# lv_io_main_connector.net
KiCad netlist of a schematic drawn in Altium Designer
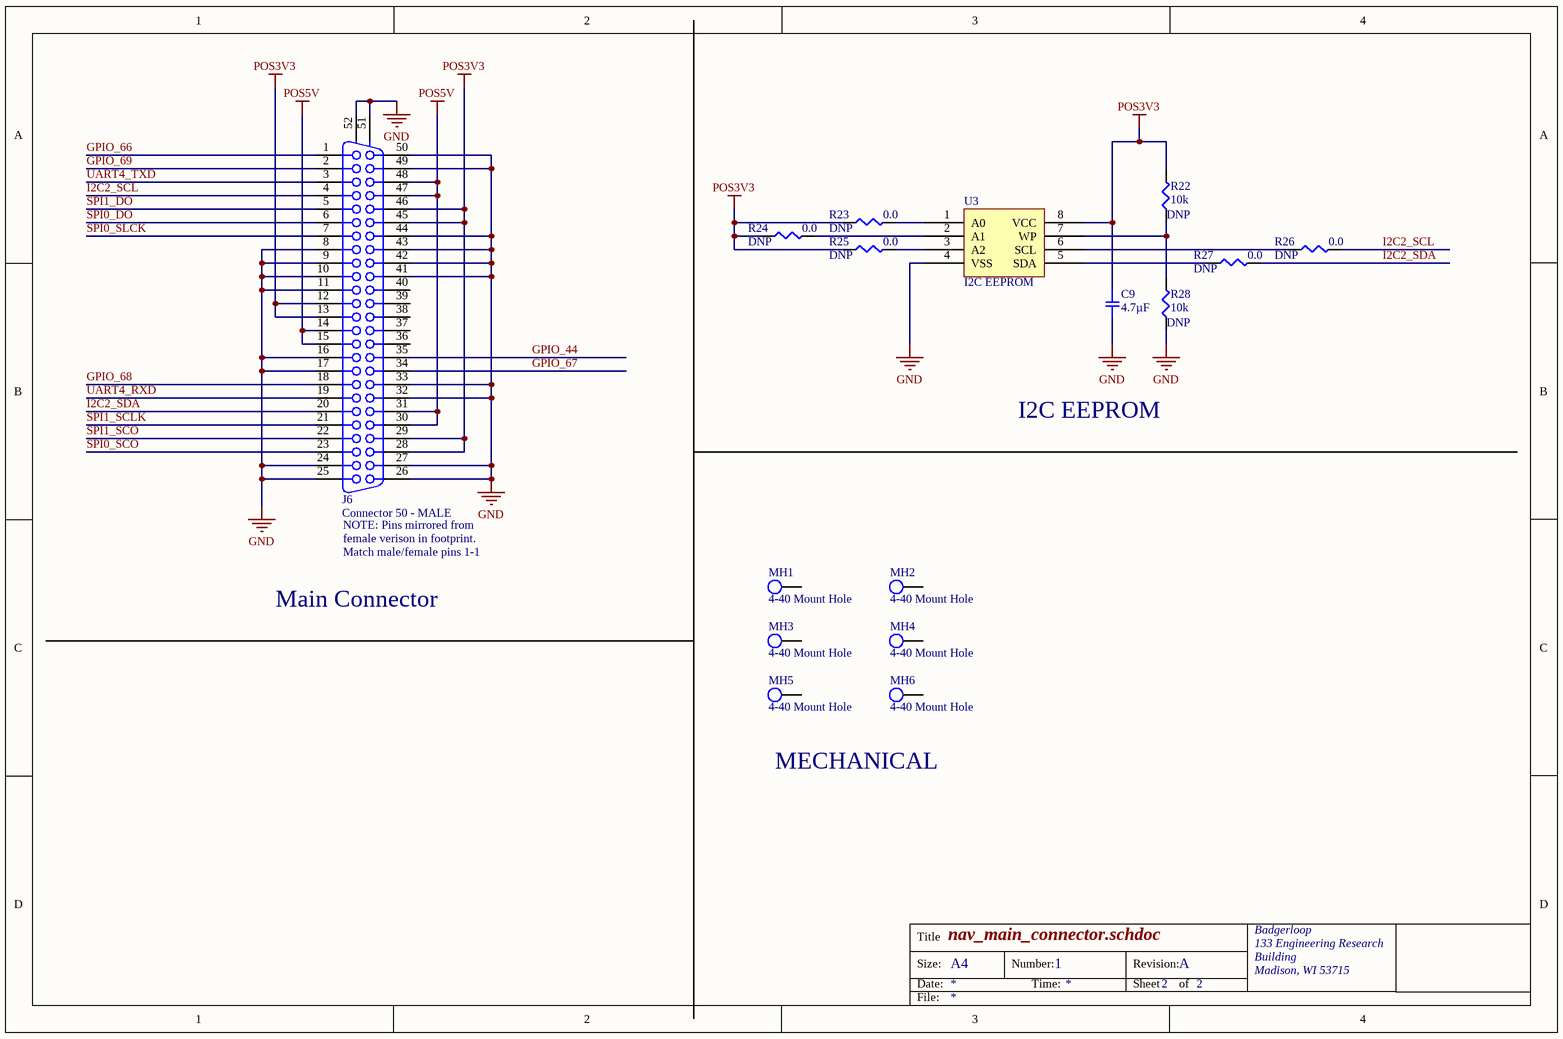
[diagram p0: lv_io_main_connector.SchDoc]

(export (version "E")
  (design (tool "Eeschema 10.0.6"))
  (components
    (comp (ref "C9")
      (value "4.7µF")
      (footprint "SMD-0805C")
      (description "CAP CER 4.7UF 16V X7R 0805")
      (fields
        (field (name "DIGI-KEY PART NUMBER") "490-10557-1-ND")
        (field (name "PART NUMBER") "GCJ21BR71C475KA01L")
      )
      (libsource (lib "capacitor") (part "GCJ21BR71C475KA01L"))
    )
    (comp (ref "J6")
      (value "Connector 50 - MALE")
      (footprint "050DSUB1.27-H96-MALE")
      (description "Receptacle Header Assemby")
      (fields (field (name "MANUFACTURER") "HARTING"))
      (libsource (lib "temp") (part "Connector 50 - MALE"))
    )
    (comp (ref "MH1")
      (value "4-40 Mount Hole")
      (footprint "MH")
      (libsource (lib "misc") (part "4-40 Mount Hole"))
    )
    (comp (ref "MH2")
      (value "4-40 Mount Hole")
      (footprint "MH")
      (libsource (lib "misc") (part "4-40 Mount Hole"))
    )
    (comp (ref "MH3")
      (value "4-40 Mount Hole")
      (footprint "MH")
      (libsource (lib "misc") (part "4-40 Mount Hole"))
    )
    (comp (ref "MH4")
      (value "4-40 Mount Hole")
      (footprint "MH")
      (libsource (lib "misc") (part "4-40 Mount Hole"))
    )
    (comp (ref "MH5")
      (value "4-40 Mount Hole")
      (footprint "MH")
      (libsource (lib "misc") (part "4-40 Mount Hole"))
    )
    (comp (ref "MH6")
      (value "4-40 Mount Hole")
      (footprint "MH")
      (libsource (lib "misc") (part "4-40 Mount Hole"))
    )
    (comp (ref "R22")
      (value "10k")
      (footprint "SMD-0402-RES")
      (description "RES SMD 10K OHM 5% 1/10W 0402")
      (fields
        (field (name "PART NUMBER") "ERJ-2GEJ103X")
        (field (name "DIGI-KEY PART NUMBER") "P10KJCT-ND")
        (field (name "DNP") "DNP")
      )
      (libsource (lib "resistor") (part "ERJ-2GEJ103X"))
    )
    (comp (ref "R23")
      (value "0.0")
      (footprint "SMD-0402-RES")
      (description "RES SMD 0.0OHM JUMPER 1/10W 0402")
      (fields
        (field (name "PART NUMBER") "ERJ-2GE0R00X")
        (field (name "DIGI-KEY PART NUMBER") "P0.0JCT-ND")
        (field (name "DNP") "DNP")
      )
      (libsource (lib "resistor") (part "ERJ-2GE0R00X"))
    )
    (comp (ref "R24")
      (value "0.0")
      (footprint "SMD-0402-RES")
      (description "RES SMD 0.0OHM JUMPER 1/10W 0402")
      (fields
        (field (name "PART NUMBER") "ERJ-2GE0R00X")
        (field (name "DIGI-KEY PART NUMBER") "P0.0JCT-ND")
        (field (name "DNP") "DNP")
      )
      (libsource (lib "resistor") (part "ERJ-2GE0R00X"))
    )
    (comp (ref "R25")
      (value "0.0")
      (footprint "SMD-0402-RES")
      (description "RES SMD 0.0OHM JUMPER 1/10W 0402")
      (fields
        (field (name "PART NUMBER") "ERJ-2GE0R00X")
        (field (name "DIGI-KEY PART NUMBER") "P0.0JCT-ND")
        (field (name "DNP") "DNP")
      )
      (libsource (lib "resistor") (part "ERJ-2GE0R00X"))
    )
    (comp (ref "R26")
      (value "0.0")
      (footprint "SMD-0402-RES")
      (description "RES SMD 0.0OHM JUMPER 1/10W 0402")
      (fields
        (field (name "PART NUMBER") "ERJ-2GE0R00X")
        (field (name "DIGI-KEY PART NUMBER") "P0.0JCT-ND")
        (field (name "DNP") "DNP")
      )
      (libsource (lib "resistor") (part "ERJ-2GE0R00X"))
    )
    (comp (ref "R27")
      (value "0.0")
      (footprint "SMD-0402-RES")
      (description "RES SMD 0.0OHM JUMPER 1/10W 0402")
      (fields
        (field (name "PART NUMBER") "ERJ-2GE0R00X")
        (field (name "DIGI-KEY PART NUMBER") "P0.0JCT-ND")
        (field (name "DNP") "DNP")
      )
      (libsource (lib "resistor") (part "ERJ-2GE0R00X"))
    )
    (comp (ref "R28")
      (value "10k")
      (footprint "SMD-0402-RES")
      (description "RES SMD 10K OHM 5% 1/10W 0402")
      (fields
        (field (name "PART NUMBER") "ERJ-2GEJ103X")
        (field (name "DIGI-KEY PART NUMBER") "P10KJCT-ND")
        (field (name "DNP") "DNP")
      )
      (libsource (lib "resistor") (part "ERJ-2GEJ103X"))
    )
    (comp (ref "U3")
      (value "I2C EEPROM")
      (footprint "SOIC127P600X175-8N")
      (description "IC EEPROM 32K I2C 1MHZ 8SOIC")
      (fields (field (name "MANUFACTURER") "ON Semi"))
      (libsource (lib "ic") (part "I2C EEPROM"))
    )
  )
  (nets
    (net (code "1") (name "/GPIO_44") (class "Default")
      (node (ref "J6") (pin "35") (pinfunction "35_35") (pintype "passive"))
    )
    (net (code "2") (name "/GPIO_66") (class "Default")
      (node (ref "J6") (pin "1") (pinfunction "1_1") (pintype "passive"))
    )
    (net (code "3") (name "/GPIO_67") (class "Default")
      (node (ref "J6") (pin "34") (pinfunction "34_34") (pintype "passive"))
    )
    (net (code "4") (name "/GPIO_68") (class "Default")
      (node (ref "J6") (pin "18") (pinfunction "18_18") (pintype "passive"))
    )
    (net (code "5") (name "/GPIO_69") (class "Default")
      (node (ref "J6") (pin "2") (pinfunction "2_2") (pintype "passive"))
    )
    (net (code "6") (name "/I2C2_SCL") (class "Default")
      (node (ref "J6") (pin "4") (pinfunction "4_4") (pintype "passive"))
      (node (ref "R26") (pin "2") (pinfunction "2_2") (pintype "passive"))
    )
    (net (code "7") (name "/I2C2_SDA") (class "Default")
      (node (ref "J6") (pin "20") (pinfunction "20_20") (pintype "passive"))
      (node (ref "R27") (pin "2") (pinfunction "2_2") (pintype "passive"))
    )
    (net (code "8") (name "/SPI0_DO") (class "Default")
      (node (ref "J6") (pin "6") (pinfunction "6_6") (pintype "passive"))
    )
    (net (code "9") (name "/SPI0_SCO") (class "Default")
      (node (ref "J6") (pin "23") (pinfunction "23_23") (pintype "passive"))
    )
    (net (code "10") (name "/SPI0_SLCK") (class "Default")
      (node (ref "J6") (pin "7") (pinfunction "7_7") (pintype "passive"))
    )
    (net (code "11") (name "/SPI1_DO") (class "Default")
      (node (ref "J6") (pin "5") (pinfunction "5_5") (pintype "passive"))
    )
    (net (code "12") (name "/SPI1_SCLK") (class "Default")
      (node (ref "J6") (pin "21") (pinfunction "21_21") (pintype "passive"))
    )
    (net (code "13") (name "/SPI1_SCO") (class "Default")
      (node (ref "J6") (pin "22") (pinfunction "22_22") (pintype "passive"))
    )
    (net (code "14") (name "/UART4_RXD") (class "Default")
      (node (ref "J6") (pin "19") (pinfunction "19_19") (pintype "passive"))
    )
    (net (code "15") (name "/UART4_TXD") (class "Default")
      (node (ref "J6") (pin "3") (pinfunction "3_3") (pintype "passive"))
    )
    (net (code "16") (name "GND") (class "Default")
      (node (ref "C9") (pin "2") (pinfunction "2_2") (pintype "passive"))
      (node (ref "J6") (pin "10") (pinfunction "10_10") (pintype "passive"))
      (node (ref "J6") (pin "11") (pinfunction "11_11") (pintype "passive"))
      (node (ref "J6") (pin "16") (pinfunction "16_16") (pintype "passive"))
      (node (ref "J6") (pin "17") (pinfunction "17_17") (pintype "passive"))
      (node (ref "J6") (pin "24") (pinfunction "24_24") (pintype "passive"))
      (node (ref "J6") (pin "25") (pinfunction "25_25") (pintype "passive"))
      (node (ref "J6") (pin "26") (pinfunction "26_26") (pintype "passive"))
      (node (ref "J6") (pin "27") (pinfunction "27_27") (pintype "passive"))
      (node (ref "J6") (pin "32") (pinfunction "32_32") (pintype "passive"))
      (node (ref "J6") (pin "33") (pinfunction "33_33") (pintype "passive"))
      (node (ref "J6") (pin "41") (pinfunction "41_41") (pintype "passive"))
      (node (ref "J6") (pin "42") (pinfunction "42_42") (pintype "passive"))
      (node (ref "J6") (pin "43") (pinfunction "43_43") (pintype "passive"))
      (node (ref "J6") (pin "44") (pinfunction "44_44") (pintype "passive"))
      (node (ref "J6") (pin "49") (pinfunction "49_49") (pintype "passive"))
      (node (ref "J6") (pin "50") (pinfunction "50_50") (pintype "passive"))
      (node (ref "J6") (pin "51") (pinfunction "51_51") (pintype "passive"))
      (node (ref "J6") (pin "52") (pinfunction "52_52") (pintype "passive"))
      (node (ref "J6") (pin "8") (pinfunction "8_8") (pintype "passive"))
      (node (ref "J6") (pin "9") (pinfunction "9_9") (pintype "passive"))
      (node (ref "R28") (pin "1") (pinfunction "1_1") (pintype "passive"))
      (node (ref "U3") (pin "4") (pinfunction "VSS_4") (pintype "power_in"))
    )
    (net (code "17") (name "Net-(U3-A0)") (class "Default")
      (node (ref "R23") (pin "2") (pinfunction "2_2") (pintype "passive"))
      (node (ref "U3") (pin "1") (pinfunction "A0_1") (pintype "passive"))
    )
    (net (code "18") (name "Net-(U3-A1)") (class "Default")
      (node (ref "R24") (pin "2") (pinfunction "2_2") (pintype "passive"))
      (node (ref "U3") (pin "2") (pinfunction "A1_2") (pintype "passive"))
    )
    (net (code "19") (name "Net-(U3-A2)") (class "Default")
      (node (ref "R25") (pin "2") (pinfunction "2_2") (pintype "passive"))
      (node (ref "U3") (pin "3") (pinfunction "A2_3") (pintype "passive"))
    )
    (net (code "20") (name "Net-(U3-SCL)") (class "Default")
      (node (ref "R26") (pin "1") (pinfunction "1_1") (pintype "passive"))
      (node (ref "U3") (pin "6") (pinfunction "SCL_6") (pintype "passive"))
    )
    (net (code "21") (name "Net-(U3-SDA)") (class "Default")
      (node (ref "R27") (pin "1") (pinfunction "1_1") (pintype "passive"))
      (node (ref "U3") (pin "5") (pinfunction "SDA_5") (pintype "passive"))
    )
    (net (code "22") (name "Net-(U3-WP)") (class "Default")
      (node (ref "R22") (pin "1") (pinfunction "1_1") (pintype "passive"))
      (node (ref "R28") (pin "2") (pinfunction "2_2") (pintype "passive"))
      (node (ref "U3") (pin "7") (pinfunction "WP_7") (pintype "passive"))
    )
    (net (code "23") (name "POS3V3") (class "Default")
      (node (ref "C9") (pin "1") (pinfunction "1_1") (pintype "passive"))
      (node (ref "J6") (pin "12") (pinfunction "12_12") (pintype "passive"))
      (node (ref "J6") (pin "13") (pinfunction "13_13") (pintype "passive"))
      (node (ref "J6") (pin "28") (pinfunction "28_28") (pintype "passive"))
      (node (ref "J6") (pin "29") (pinfunction "29_29") (pintype "passive"))
      (node (ref "J6") (pin "45") (pinfunction "45_45") (pintype "passive"))
      (node (ref "J6") (pin "46") (pinfunction "46_46") (pintype "passive"))
      (node (ref "R22") (pin "2") (pinfunction "2_2") (pintype "passive"))
      (node (ref "R23") (pin "1") (pinfunction "1_1") (pintype "passive"))
      (node (ref "R24") (pin "1") (pinfunction "1_1") (pintype "passive"))
      (node (ref "R25") (pin "1") (pinfunction "1_1") (pintype "passive"))
      (node (ref "U3") (pin "8") (pinfunction "VCC_8") (pintype "power_in"))
    )
    (net (code "24") (name "POS5V") (class "Default")
      (node (ref "J6") (pin "14") (pinfunction "14_14") (pintype "passive"))
      (node (ref "J6") (pin "15") (pinfunction "15_15") (pintype "passive"))
      (node (ref "J6") (pin "30") (pinfunction "30_30") (pintype "passive"))
      (node (ref "J6") (pin "31") (pinfunction "31_31") (pintype "passive"))
      (node (ref "J6") (pin "47") (pinfunction "47_47") (pintype "passive"))
      (node (ref "J6") (pin "48") (pinfunction "48_48") (pintype "passive"))
    )
    (net (code "25") (name "unconnected-(J6-Pad36)") (class "Default")
      (node (ref "J6") (pin "36") (pinfunction "36_36") (pintype "passive"))
    )
    (net (code "26") (name "unconnected-(J6-Pad37)") (class "Default")
      (node (ref "J6") (pin "37") (pinfunction "37_37") (pintype "passive"))
    )
    (net (code "27") (name "unconnected-(J6-Pad38)") (class "Default")
      (node (ref "J6") (pin "38") (pinfunction "38_38") (pintype "passive"))
    )
    (net (code "28") (name "unconnected-(J6-Pad39)") (class "Default")
      (node (ref "J6") (pin "39") (pinfunction "39_39") (pintype "passive"))
    )
    (net (code "29") (name "unconnected-(J6-Pad40)") (class "Default")
      (node (ref "J6") (pin "40") (pinfunction "40_40") (pintype "passive"))
    )
    (net (code "30") (name "unconnected-(MH1-Pad46)") (class "Default")
      (node (ref "MH1") (pin "46") (pinfunction "46_46") (pintype "passive"))
    )
    (net (code "31") (name "unconnected-(MH2-Pad46)") (class "Default")
      (node (ref "MH2") (pin "46") (pinfunction "46_46") (pintype "passive"))
    )
    (net (code "32") (name "unconnected-(MH3-Pad46)") (class "Default")
      (node (ref "MH3") (pin "46") (pinfunction "46_46") (pintype "passive"))
    )
    (net (code "33") (name "unconnected-(MH4-Pad46)") (class "Default")
      (node (ref "MH4") (pin "46") (pinfunction "46_46") (pintype "passive"))
    )
    (net (code "34") (name "unconnected-(MH5-Pad46)") (class "Default")
      (node (ref "MH5") (pin "46") (pinfunction "46_46") (pintype "passive"))
    )
    (net (code "35") (name "unconnected-(MH6-Pad46)") (class "Default")
      (node (ref "MH6") (pin "46") (pinfunction "46_46") (pintype "passive"))
    )
  )
)
